# ledboard_noISP.net
KiCad netlist of a schematic drawn in EAGLE
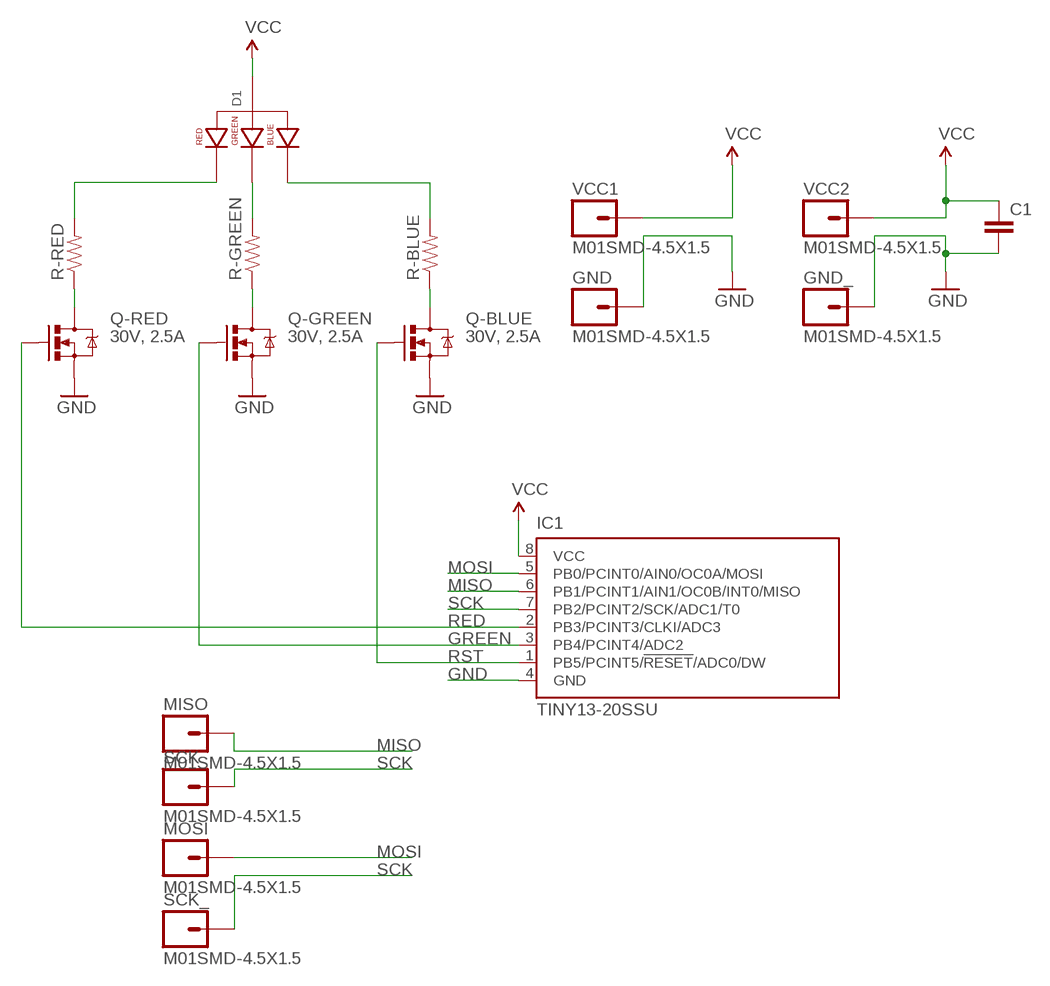
[diagram p0: schematic, sheet 1]

(export (version "E")
  (design (tool "Eeschema 10.0.6"))
  (components
    (comp (ref "C1")
      (value "CAP0805")
      (footprint "eagle-import:0805")
      (libsource (lib "eagle-import") (part "CAP0805"))
    )
    (comp (ref "D1")
      (value "LED-RGB-CA-THRUCLEAR")
      (footprint "eagle-import:LED-RGB-THRU")
      (libsource (lib "eagle-import") (part "LED-RGB-CA-THRUCLEAR"))
    )
    (comp (ref "GND")
      (value "M01SMD-4.5X1.5")
      (footprint "eagle-import:PAD-1.5X4.5")
      (libsource (lib "eagle-import") (part "M01SMD-4.5X1.5"))
    )
    (comp (ref "GND_")
      (value "M01SMD-4.5X1.5")
      (footprint "eagle-import:PAD-1.5X4.5")
      (libsource (lib "eagle-import") (part "M01SMD-4.5X1.5"))
    )
    (comp (ref "IC1")
      (value "TINY13-20SSU")
      (footprint "eagle-import:8S1")
      (fields (field (name "MPN") "ATTINY13-20SSU"))
      (libsource (lib "eagle-import") (part "TINY13SSU-20"))
    )
    (comp (ref "MISO")
      (value "M01SMD-4.5X1.5")
      (footprint "eagle-import:PAD-1.5X4.5")
      (libsource (lib "eagle-import") (part "M01SMD-4.5X1.5"))
    )
    (comp (ref "MOSI")
      (value "M01SMD-4.5X1.5")
      (footprint "eagle-import:PAD-1.5X4.5")
      (libsource (lib "eagle-import") (part "M01SMD-4.5X1.5"))
    )
    (comp (ref "Q-BLUE")
      (value "30V, 2.5A")
      (footprint "eagle-import:SOT23")
      (libsource (lib "eagle-import") (part "MOSFET-NCHANNELBSS123LT1G"))
    )
    (comp (ref "Q-GREEN")
      (value "30V, 2.5A")
      (footprint "eagle-import:SOT23")
      (libsource (lib "eagle-import") (part "MOSFET-NCHANNELBSS123LT1G"))
    )
    (comp (ref "Q-RED")
      (value "30V, 2.5A")
      (footprint "eagle-import:SOT23")
      (libsource (lib "eagle-import") (part "MOSFET-NCHANNELBSS123LT1G"))
    )
    (comp (ref "R-BLUE")
      (value "RESISTOR0603")
      (footprint "eagle-import:0603-RES")
      (libsource (lib "eagle-import") (part "RESISTOR0603"))
    )
    (comp (ref "R-GREEN")
      (value "RESISTOR0603")
      (footprint "eagle-import:0603-RES")
      (libsource (lib "eagle-import") (part "RESISTOR0603"))
    )
    (comp (ref "R-RED")
      (value "RESISTOR0603")
      (footprint "eagle-import:0603-RES")
      (libsource (lib "eagle-import") (part "RESISTOR0603"))
    )
    (comp (ref "SCK")
      (value "M01SMD-4.5X1.5")
      (footprint "eagle-import:PAD-1.5X4.5")
      (libsource (lib "eagle-import") (part "M01SMD-4.5X1.5"))
    )
    (comp (ref "SCK_")
      (value "M01SMD-4.5X1.5")
      (footprint "eagle-import:PAD-1.5X4.5")
      (libsource (lib "eagle-import") (part "M01SMD-4.5X1.5"))
    )
    (comp (ref "VCC1")
      (value "M01SMD-4.5X1.5")
      (footprint "eagle-import:PAD-1.5X4.5")
      (libsource (lib "eagle-import") (part "M01SMD-4.5X1.5"))
    )
    (comp (ref "VCC2")
      (value "M01SMD-4.5X1.5")
      (footprint "eagle-import:PAD-1.5X4.5")
      (libsource (lib "eagle-import") (part "M01SMD-4.5X1.5"))
    )
  )
  (nets
    (net (code "1") (name "/GREEN") (class "Default")
      (node (ref "IC1") (pin "3") (pinfunction "PB4/PCINT4/ADC2_3") (pintype "bidirectional"))
      (node (ref "Q-GREEN") (pin "1") (pinfunction "G_1") (pintype "passive"))
    )
    (net (code "2") (name "/MISO") (class "Default")
      (node (ref "IC1") (pin "6") (pinfunction "PB1/PCINT1/AIN1/OC0B/INT0/MISO_6") (pintype "bidirectional"))
      (node (ref "MISO") (pin "P$1") (pinfunction "1_P$1") (pintype "passive"))
    )
    (net (code "3") (name "/MOSI") (class "Default")
      (node (ref "IC1") (pin "5") (pinfunction "PB0/PCINT0/AIN0/OC0A/MOSI_5") (pintype "bidirectional"))
      (node (ref "MOSI") (pin "P$1") (pinfunction "1_P$1") (pintype "passive"))
    )
    (net (code "4") (name "/RED") (class "Default")
      (node (ref "IC1") (pin "2") (pinfunction "PB3/PCINT3/CLKI/ADC3_2") (pintype "bidirectional"))
      (node (ref "Q-RED") (pin "1") (pinfunction "G_1") (pintype "passive"))
    )
    (net (code "5") (name "/RST") (class "Default")
      (node (ref "IC1") (pin "1") (pinfunction "PB5/PCINT5/~{RESET}/ADC0/DW_1") (pintype "bidirectional"))
      (node (ref "Q-BLUE") (pin "1") (pinfunction "G_1") (pintype "passive"))
    )
    (net (code "6") (name "/SCK") (class "Default")
      (node (ref "IC1") (pin "7") (pinfunction "PB2/PCINT2/SCK/ADC1/T0_7") (pintype "bidirectional"))
      (node (ref "SCK") (pin "P$1") (pinfunction "1_P$1") (pintype "passive"))
      (node (ref "SCK_") (pin "P$1") (pinfunction "1_P$1") (pintype "passive"))
    )
    (net (code "7") (name "GND") (class "Default")
      (node (ref "C1") (pin "2") (pinfunction "2_2") (pintype "passive"))
      (node (ref "GND") (pin "P$1") (pinfunction "1_P$1") (pintype "passive"))
      (node (ref "GND_") (pin "P$1") (pinfunction "1_P$1") (pintype "passive"))
      (node (ref "IC1") (pin "4") (pinfunction "GND_4") (pintype "power_in"))
      (node (ref "Q-BLUE") (pin "2") (pinfunction "S_2") (pintype "passive"))
      (node (ref "Q-GREEN") (pin "2") (pinfunction "S_2") (pintype "passive"))
      (node (ref "Q-RED") (pin "2") (pinfunction "S_2") (pintype "passive"))
    )
    (net (code "8") (name "Net-(D1-BLUE_CATHODE)") (class "Default")
      (node (ref "D1") (pin "4") (pinfunction "BLUE_CATHODE_4") (pintype "bidirectional"))
      (node (ref "R-BLUE") (pin "2") (pinfunction "2_2") (pintype "passive"))
    )
    (net (code "9") (name "Net-(D1-GREEN_CATHODE)") (class "Default")
      (node (ref "D1") (pin "3") (pinfunction "GREEN_CATHODE_3") (pintype "bidirectional"))
      (node (ref "R-GREEN") (pin "2") (pinfunction "2_2") (pintype "passive"))
    )
    (net (code "10") (name "Net-(D1-RED_CATHODE)") (class "Default")
      (node (ref "D1") (pin "1") (pinfunction "RED_CATHODE_1") (pintype "bidirectional"))
      (node (ref "R-RED") (pin "2") (pinfunction "2_2") (pintype "passive"))
    )
    (net (code "11") (name "Net-(Q-BLUE-D)") (class "Default")
      (node (ref "Q-BLUE") (pin "3") (pinfunction "D_3") (pintype "passive"))
      (node (ref "R-BLUE") (pin "1") (pinfunction "1_1") (pintype "passive"))
    )
    (net (code "12") (name "Net-(Q-GREEN-D)") (class "Default")
      (node (ref "Q-GREEN") (pin "3") (pinfunction "D_3") (pintype "passive"))
      (node (ref "R-GREEN") (pin "1") (pinfunction "1_1") (pintype "passive"))
    )
    (net (code "13") (name "Net-(Q-RED-D)") (class "Default")
      (node (ref "Q-RED") (pin "3") (pinfunction "D_3") (pintype "passive"))
      (node (ref "R-RED") (pin "1") (pinfunction "1_1") (pintype "passive"))
    )
    (net (code "14") (name "VCC") (class "Default")
      (node (ref "C1") (pin "1") (pinfunction "1_1") (pintype "passive"))
      (node (ref "D1") (pin "2") (pinfunction "ANODE_2") (pintype "bidirectional"))
      (node (ref "IC1") (pin "8") (pinfunction "VCC_8") (pintype "power_in"))
      (node (ref "VCC1") (pin "P$1") (pinfunction "1_P$1") (pintype "passive"))
      (node (ref "VCC2") (pin "P$1") (pinfunction "1_P$1") (pintype "passive"))
    )
  )
)
